# Sensors.net
KiCad netlist of a schematic drawn in Altium Designer
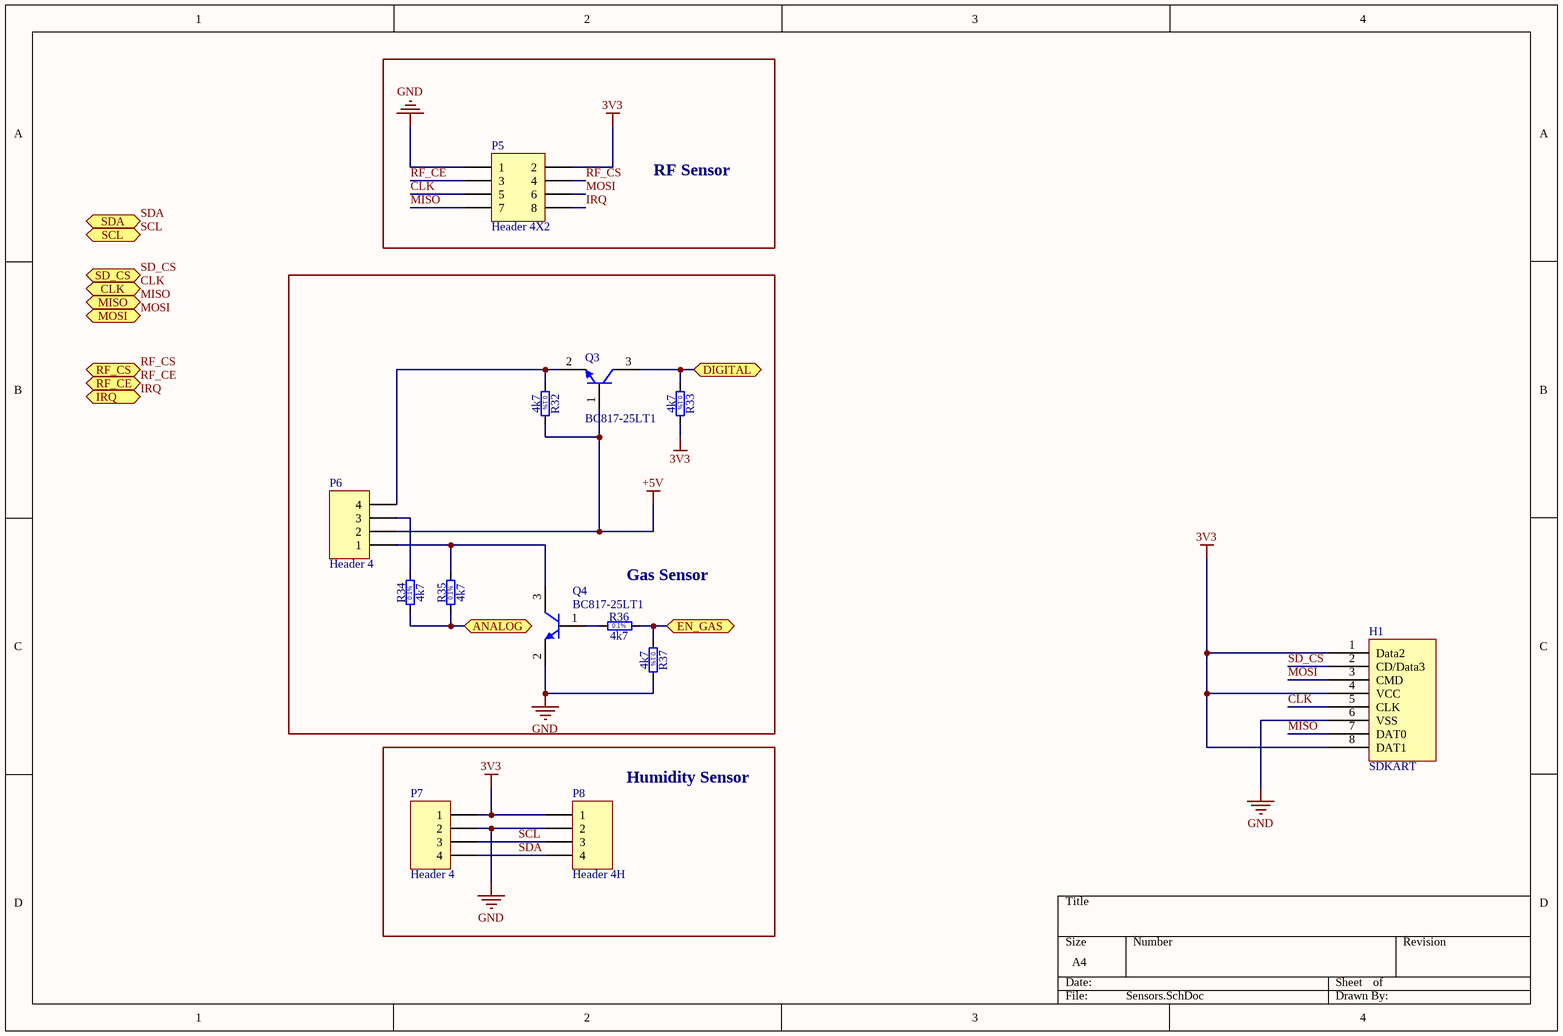
[diagram p0: Sensors.SchDoc]

(export (version "E")
  (design (tool "Eeschema 10.0.6"))
  (components
    (comp (ref "H1")
      (value "SDKART")
      (footprint "PCBComponent_1")
      (libsource (lib "Integrated_Library") (part "SDKART"))
    )
    (comp (ref "P5")
      (value "Header 4X2")
      (footprint "HDR2X4")
      (description "Header, 4-Pin, Dual row")
      (fields (field (name "PUBLISHER") "Altium Limited"))
      (libsource (lib "Miscellaneous Connectors") (part "Header 4X2"))
    )
    (comp (ref "P6")
      (value "Header 4")
      (footprint "HDR1X4")
      (description "Header, 4-Pin")
      (fields (field (name "PUBLISHER") "Altium Limited"))
      (libsource (lib "Miscellaneous Connectors") (part "Header 4"))
    )
    (comp (ref "P7")
      (value "Header 4")
      (footprint "HDR1X4")
      (description "Header, 4-Pin")
      (fields (field (name "PUBLISHER") "Altium Limited"))
      (libsource (lib "") (part "Header 4_1"))
    )
    (comp (ref "P8")
      (value "Header 4H")
      (footprint "HDR1X4H")
      (description "Header, 4-Pin, Right Angle")
      (fields (field (name "PUBLISHER") "Altium Limited"))
      (libsource (lib "Miscellaneous Connectors") (part "Header 4H"))
    )
    (comp (ref "Q3")
      (value "BC817-25LT1")
      (footprint "ONSC-SOT-23-3-318-08_V")
      (description "General Purpose Transistor, NPN Silicon, 3-Pin SOT-23, Tape and Reel")
      (fields (field (name "MANUFACTURER") "On Semiconductor"))
      (libsource (lib "ON Semi General Purpose Transistors") (part "BC817-25LT1"))
    )
    (comp (ref "Q4")
      (value "BC817-25LT1")
      (footprint "ONSC-SOT-23-3-318-08_V")
      (description "General Purpose Transistor, NPN Silicon, 3-Pin SOT-23, Tape and Reel")
      (fields (field (name "MANUFACTURER") "On Semiconductor"))
      (libsource (lib "ON Semi General Purpose Transistors") (part "BC817-25LT1"))
    )
    (comp (ref "R32")
      (value "4k7")
      (footprint "RESC2012X60N")
      (description "Resistor - 0.1%")
      (fields
        (field (name "PART NUMBER") "R0805_1K1_0.1%_0.1W_10PPM")
        (field (name "POWER") "0.1W")
        (field (name "AUTHOR") "CERN DEM JLC")
      )
      (libsource (lib "Resistors") (part "Resistor - 0.1%"))
    )
    (comp (ref "R33")
      (value "4k7")
      (footprint "RESC2012X60N")
      (description "Resistor - 0.1%")
      (fields
        (field (name "PART NUMBER") "R0805_1K1_0.1%_0.1W_10PPM")
        (field (name "POWER") "0.1W")
        (field (name "AUTHOR") "CERN DEM JLC")
      )
      (libsource (lib "Resistors") (part "Resistor - 0.1%"))
    )
    (comp (ref "R34")
      (value "4k7")
      (footprint "RESC2012X60N")
      (description "Resistor - 0.1%")
      (fields
        (field (name "PART NUMBER") "R0805_1K1_0.1%_0.1W_10PPM")
        (field (name "POWER") "0.1W")
        (field (name "AUTHOR") "CERN DEM JLC")
      )
      (libsource (lib "Resistors") (part "Resistor - 0.1%"))
    )
    (comp (ref "R35")
      (value "4k7")
      (footprint "RESC2012X60N")
      (description "Resistor - 0.1%")
      (fields
        (field (name "PART NUMBER") "R0805_1K1_0.1%_0.1W_10PPM")
        (field (name "POWER") "0.1W")
        (field (name "AUTHOR") "CERN DEM JLC")
      )
      (libsource (lib "Resistors") (part "Resistor - 0.1%"))
    )
    (comp (ref "R36")
      (value "4k7")
      (footprint "RESC2012X60N")
      (description "Resistor - 0.1%")
      (fields
        (field (name "PART NUMBER") "R0805_1K1_0.1%_0.1W_10PPM")
        (field (name "POWER") "0.1W")
        (field (name "AUTHOR") "CERN DEM JLC")
      )
      (libsource (lib "Resistors") (part "Resistor - 0.1%"))
    )
    (comp (ref "R37")
      (value "4k7")
      (footprint "RESC2012X60N")
      (description "Resistor - 0.1%")
      (fields
        (field (name "PART NUMBER") "R0805_1K1_0.1%_0.1W_10PPM")
        (field (name "POWER") "0.1W")
        (field (name "AUTHOR") "CERN DEM JLC")
      )
      (libsource (lib "Resistors") (part "Resistor - 0.1%"))
    )
  )
  (nets
    (net (code "1") (name "+5V") (class "Default")
      (node (ref "P6") (pin "2") (pinfunction "2_2") (pintype "passive"))
      (node (ref "Q3") (pin "1") (pinfunction "B_1") (pintype "passive"))
      (node (ref "R32") (pin "2") (pinfunction "2_2") (pintype "passive"))
    )
    (net (code "2") (name "/ANALOG") (class "Default")
      (node (ref "R34") (pin "1") (pinfunction "1_1") (pintype "passive"))
      (node (ref "R35") (pin "1") (pinfunction "1_1") (pintype "passive"))
    )
    (net (code "3") (name "/CLK") (class "Default")
      (node (ref "H1") (pin "5") (pinfunction "CLK_5") (pintype "passive"))
      (node (ref "P5") (pin "5") (pinfunction "5_5") (pintype "passive"))
    )
    (net (code "4") (name "/DIGITAL") (class "Default")
      (node (ref "Q3") (pin "3") (pinfunction "C_3") (pintype "passive"))
      (node (ref "R33") (pin "1") (pinfunction "1_1") (pintype "passive"))
    )
    (net (code "5") (name "/EN_GAS") (class "Default")
      (node (ref "R36") (pin "2") (pinfunction "2_2") (pintype "passive"))
      (node (ref "R37") (pin "1") (pinfunction "1_1") (pintype "passive"))
    )
    (net (code "6") (name "/IRQ") (class "Default")
      (node (ref "P5") (pin "8") (pinfunction "8_8") (pintype "passive"))
    )
    (net (code "7") (name "/MISO") (class "Default")
      (node (ref "H1") (pin "7") (pinfunction "DAT0_7") (pintype "passive"))
      (node (ref "P5") (pin "7") (pinfunction "7_7") (pintype "passive"))
    )
    (net (code "8") (name "/MOSI") (class "Default")
      (node (ref "H1") (pin "3") (pinfunction "CMD_3") (pintype "passive"))
      (node (ref "P5") (pin "6") (pinfunction "6_6") (pintype "passive"))
    )
    (net (code "9") (name "/RF_CE") (class "Default")
      (node (ref "P5") (pin "3") (pinfunction "3_3") (pintype "passive"))
    )
    (net (code "10") (name "/RF_CS") (class "Default")
      (node (ref "P5") (pin "4") (pinfunction "4_4") (pintype "passive"))
    )
    (net (code "11") (name "/SCL") (class "Default")
      (node (ref "P7") (pin "3") (pinfunction "3_3") (pintype "passive"))
      (node (ref "P8") (pin "3") (pinfunction "3_3") (pintype "passive"))
    )
    (net (code "12") (name "/SDA") (class "Default")
      (node (ref "P7") (pin "4") (pinfunction "4_4") (pintype "passive"))
      (node (ref "P8") (pin "4") (pinfunction "4_4") (pintype "passive"))
    )
    (net (code "13") (name "/SD_CS") (class "Default")
      (node (ref "H1") (pin "2") (pinfunction "CD/Data3_2") (pintype "passive"))
    )
    (net (code "14") (name "3V3") (class "Default")
      (node (ref "H1") (pin "1") (pinfunction "Data2_1") (pintype "passive"))
      (node (ref "H1") (pin "4") (pinfunction "VCC_4") (pintype "passive"))
      (node (ref "H1") (pin "8") (pinfunction "DAT1_8") (pintype "passive"))
      (node (ref "P5") (pin "2") (pinfunction "2_2") (pintype "passive"))
      (node (ref "P7") (pin "1") (pinfunction "1_1") (pintype "passive"))
      (node (ref "P8") (pin "1") (pinfunction "1_1") (pintype "passive"))
      (node (ref "R33") (pin "2") (pinfunction "2_2") (pintype "passive"))
    )
    (net (code "15") (name "GND") (class "Default")
      (node (ref "H1") (pin "6") (pinfunction "VSS_6") (pintype "passive"))
      (node (ref "P5") (pin "1") (pinfunction "1_1") (pintype "passive"))
      (node (ref "P7") (pin "2") (pinfunction "2_2") (pintype "passive"))
      (node (ref "P8") (pin "2") (pinfunction "2_2") (pintype "passive"))
      (node (ref "Q4") (pin "2") (pinfunction "E_2") (pintype "passive"))
      (node (ref "R37") (pin "2") (pinfunction "2_2") (pintype "passive"))
    )
    (net (code "16") (name "Net-(P6-Pad3)") (class "Default")
      (node (ref "P6") (pin "3") (pinfunction "3_3") (pintype "passive"))
      (node (ref "R34") (pin "2") (pinfunction "2_2") (pintype "passive"))
    )
    (net (code "17") (name "Net-(Q3-E)") (class "Default")
      (node (ref "P6") (pin "4") (pinfunction "4_4") (pintype "passive"))
      (node (ref "Q3") (pin "2") (pinfunction "E_2") (pintype "passive"))
      (node (ref "R32") (pin "1") (pinfunction "1_1") (pintype "passive"))
    )
    (net (code "18") (name "Net-(Q4-B)") (class "Default")
      (node (ref "Q4") (pin "1") (pinfunction "B_1") (pintype "passive"))
      (node (ref "R36") (pin "1") (pinfunction "1_1") (pintype "passive"))
    )
    (net (code "19") (name "Net-(Q4-C)") (class "Default")
      (node (ref "P6") (pin "1") (pinfunction "1_1") (pintype "passive"))
      (node (ref "Q4") (pin "3") (pinfunction "C_3") (pintype "passive"))
      (node (ref "R35") (pin "2") (pinfunction "2_2") (pintype "passive"))
    )
  )
)
